# PWR_PROT_AND_VI_SENSE.net
KiCad netlist of a schematic drawn in Altium Designer
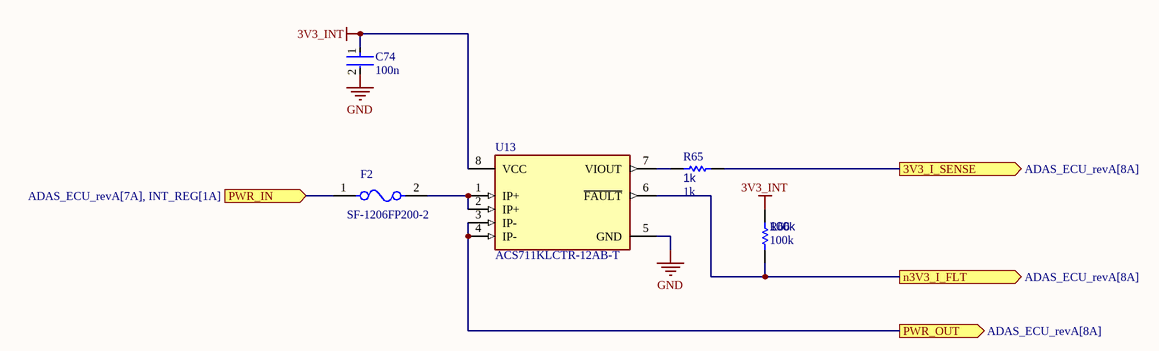
[diagram p0: PWR_PROT_AND_VI_SENSE.SchDoc]

(export (version "E")
  (design (tool "Eeschema 10.0.6"))
  (components
    (comp (ref "C74")
      (value "100n")
      (footprint "FP-0402-L_1_0_0_05-W_0_5-IPC_A")
      (description "LARGE PADS, 0402 CAP, CHANGE COMMENT TO MATCH REAL P/N")
      (libsource (lib "Space Concordia") (part "b4654b650e69147ec39a6b967a45e02"))
    )
    (comp (ref "F2")
      (value "SF-1206FP200-2")
      (footprint "FP-SF-1206FP-MFG")
      (description "FUSE BOARD MOUNT 2A 63VDC 1206")
      (libsource (lib "Altium Content Vault") (part "5bcf9b9f640e542cf0359d10258e979"))
    )
    (comp (ref "R65")
      (value "1k")
      (footprint "R0603B")
      (description "Resistor")
      (fields (field (name "ALTIUM_VALUE") "1k"))
      (libsource (lib "Space Concordia") (part "Resistor"))
    )
    (comp (ref "R66")
      (value "100k")
      (footprint "R0603B")
      (description "Resistor")
      (fields (field (name "ALTIUM_VALUE") "100k"))
      (libsource (lib "Space Concordia") (part "Resistor"))
    )
    (comp (ref "U13")
      (value "ACS711KLCTR-12AB-T")
      (footprint "FP-LC-8-IPC_C")
      (description "SENSOR CURRENT HALL 12.5A AC/DC")
      (libsource (lib "Altium Content Vault") (part "b5e82308d4912bad35d89a98a7a92f9"))
    )
  )
  (nets
    (net (code "1") (name "/3V3_I_SENSE") (class "Default")
      (node (ref "R65") (pin "2") (pinfunction "2_2") (pintype "passive"))
    )
    (net (code "2") (name "/PWR_IN") (class "Default")
      (node (ref "F2") (pin "1") (pinfunction "1_1") (pintype "passive"))
    )
    (net (code "3") (name "/PWR_OUT") (class "Default")
      (node (ref "U13") (pin "3") (pinfunction "IP-_3") (pintype "input"))
      (node (ref "U13") (pin "4") (pinfunction "IP-_4") (pintype "input"))
    )
    (net (code "4") (name "/n3V3_I_FLT") (class "Default")
      (node (ref "R66") (pin "1") (pinfunction "1_1") (pintype "passive"))
      (node (ref "U13") (pin "6") (pinfunction "~{FAULT}_6") (pintype "output"))
    )
    (net (code "5") (name "3V3_INT") (class "Default")
      (node (ref "C74") (pin "1") (pinfunction "1_1") (pintype "passive"))
      (node (ref "R66") (pin "2") (pinfunction "2_2") (pintype "passive"))
      (node (ref "U13") (pin "8") (pinfunction "VCC_8") (pintype "power_in"))
    )
    (net (code "6") (name "GND") (class "Default")
      (node (ref "C74") (pin "2") (pinfunction "2_2") (pintype "passive"))
      (node (ref "U13") (pin "5") (pinfunction "GND_5") (pintype "power_in"))
    )
    (net (code "7") (name "Net-(F2-Pad2)") (class "Default")
      (node (ref "F2") (pin "2") (pinfunction "2_2") (pintype "passive"))
      (node (ref "U13") (pin "1") (pinfunction "IP+_1") (pintype "input"))
      (node (ref "U13") (pin "2") (pinfunction "IP+_2") (pintype "input"))
    )
    (net (code "8") (name "Net-(U13-VIOUT)") (class "Default")
      (node (ref "R65") (pin "1") (pinfunction "1_1") (pintype "passive"))
      (node (ref "U13") (pin "7") (pinfunction "VIOUT_7") (pintype "output"))
    )
  )
)
